# DACs.net
KiCad netlist of a schematic drawn in Altium Designer
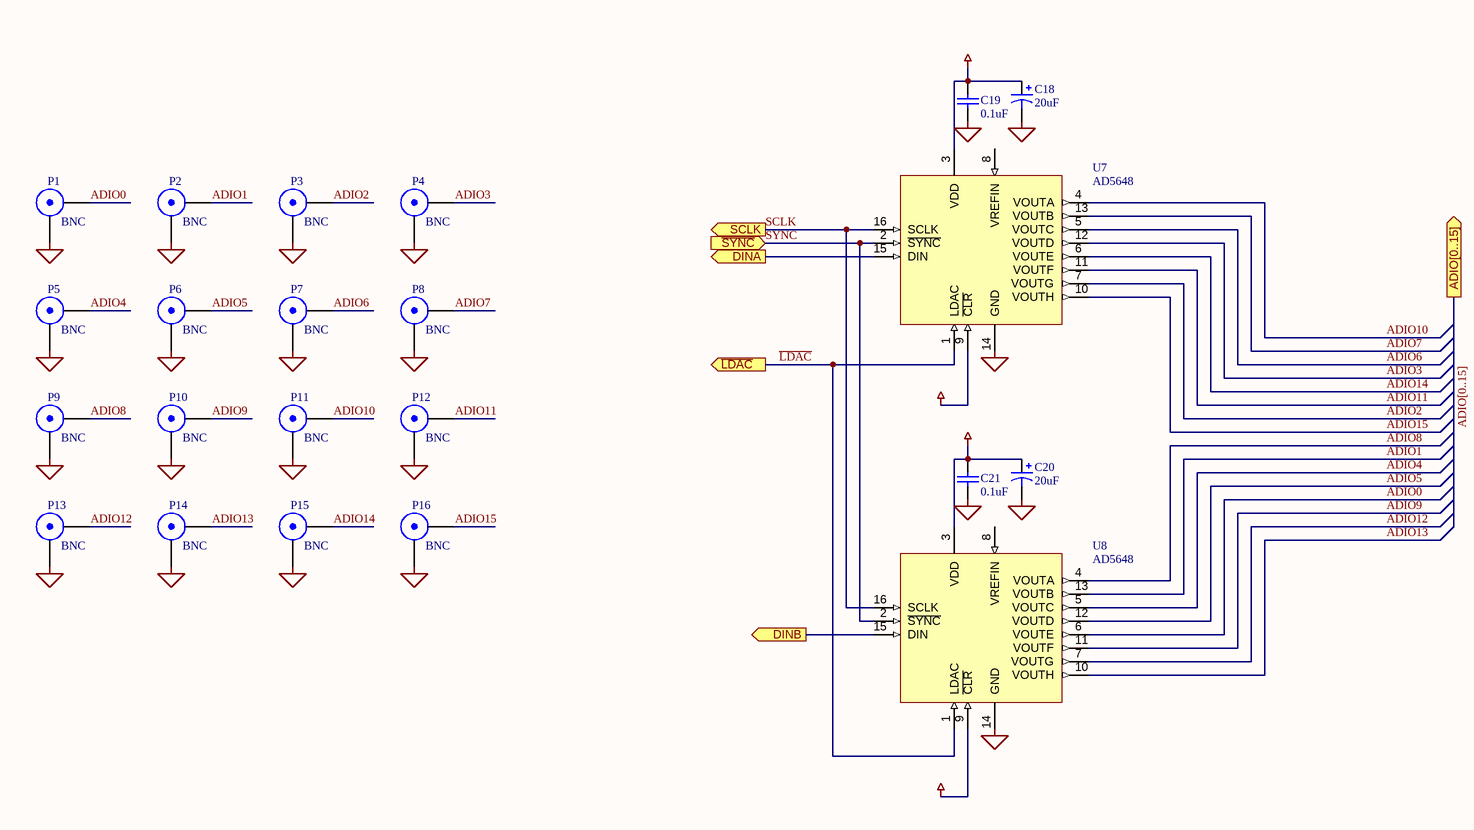
[diagram p0: DACs.SCHDOC]

(export (version "E")
  (design (tool "Eeschema 10.0.6"))
  (components
    (comp (ref "C18")
      (value "20uF")
      (footprint "C")
      (description "Polarized Capacitor (Radial)")
      (fields (field (name "Comment") "Cap Pol1") (field (name "PUBLISHER") "Altium Limited"))
      (libsource (lib "Miscellaneous Devices") (part "Cap Pol1"))
    )
    (comp (ref "C19")
      (value "0.1uF")
      (footprint "CC1005-0402")
      (description "Capacitor")
      (fields
        (field (name "MANUFACTURER") "Generic Components")
        (field (name "Comment") "Cap")
        (field (name "PUBLISHER") "Altium Limited")
      )
      (libsource (lib "Miscellaneous Devices") (part "Cap"))
    )
    (comp (ref "C20")
      (value "20uF")
      (footprint "C")
      (description "Polarized Capacitor (Radial)")
      (fields (field (name "Comment") "Cap Pol1") (field (name "PUBLISHER") "Altium Limited"))
      (libsource (lib "Miscellaneous Devices") (part "Cap Pol1"))
    )
    (comp (ref "C21")
      (value "0.1uF")
      (footprint "CC1005-0402")
      (description "Capacitor")
      (fields
        (field (name "MANUFACTURER") "Generic Components")
        (field (name "Comment") "Cap")
        (field (name "PUBLISHER") "Altium Limited")
      )
      (libsource (lib "Miscellaneous Devices") (part "Cap"))
    )
    (comp (ref "P1")
      (value "BNC")
      (footprint "Vertical BNC 227699-1")
      (description "BNC Elbow Connector")
      (fields (field (name "MANUFACTURER") "Generic Components") (field (name "PUBLISHER") "Altium Limited"))
      (libsource (lib "Miscellaneous Connectors") (part "BNC"))
    )
    (comp (ref "P2")
      (value "BNC")
      (footprint "Vertical BNC 227699-1")
      (description "BNC Elbow Connector")
      (fields (field (name "MANUFACTURER") "Generic Components") (field (name "PUBLISHER") "Altium Limited"))
      (libsource (lib "Miscellaneous Connectors") (part "BNC"))
    )
    (comp (ref "P3")
      (value "BNC")
      (footprint "Vertical BNC 227699-1")
      (description "BNC Elbow Connector")
      (fields (field (name "MANUFACTURER") "Generic Components") (field (name "PUBLISHER") "Altium Limited"))
      (libsource (lib "Miscellaneous Connectors") (part "BNC"))
    )
    (comp (ref "P4")
      (value "BNC")
      (footprint "Vertical BNC 227699-1")
      (description "BNC Elbow Connector")
      (fields (field (name "MANUFACTURER") "Generic Components") (field (name "PUBLISHER") "Altium Limited"))
      (libsource (lib "Miscellaneous Connectors") (part "BNC"))
    )
    (comp (ref "P5")
      (value "BNC")
      (footprint "Vertical BNC 227699-1")
      (description "BNC Elbow Connector")
      (fields (field (name "MANUFACTURER") "Generic Components") (field (name "PUBLISHER") "Altium Limited"))
      (libsource (lib "Miscellaneous Connectors") (part "BNC"))
    )
    (comp (ref "P6")
      (value "BNC")
      (footprint "Vertical BNC 227699-1")
      (description "BNC Elbow Connector")
      (fields (field (name "MANUFACTURER") "Generic Components") (field (name "PUBLISHER") "Altium Limited"))
      (libsource (lib "Miscellaneous Connectors") (part "BNC"))
    )
    (comp (ref "P7")
      (value "BNC")
      (footprint "Vertical BNC 227699-1")
      (description "BNC Elbow Connector")
      (fields (field (name "MANUFACTURER") "Generic Components") (field (name "PUBLISHER") "Altium Limited"))
      (libsource (lib "Miscellaneous Connectors") (part "BNC"))
    )
    (comp (ref "P8")
      (value "BNC")
      (footprint "Vertical BNC 227699-1")
      (description "BNC Elbow Connector")
      (fields (field (name "MANUFACTURER") "Generic Components") (field (name "PUBLISHER") "Altium Limited"))
      (libsource (lib "Miscellaneous Connectors") (part "BNC"))
    )
    (comp (ref "P9")
      (value "BNC")
      (footprint "Vertical BNC 227699-1")
      (description "BNC Elbow Connector")
      (fields (field (name "MANUFACTURER") "Generic Components") (field (name "PUBLISHER") "Altium Limited"))
      (libsource (lib "Miscellaneous Connectors") (part "BNC"))
    )
    (comp (ref "P10")
      (value "BNC")
      (footprint "Vertical BNC 227699-1")
      (description "BNC Elbow Connector")
      (fields (field (name "MANUFACTURER") "Generic Components") (field (name "PUBLISHER") "Altium Limited"))
      (libsource (lib "Miscellaneous Connectors") (part "BNC"))
    )
    (comp (ref "P11")
      (value "BNC")
      (footprint "Vertical BNC 227699-1")
      (description "BNC Elbow Connector")
      (fields (field (name "MANUFACTURER") "Generic Components") (field (name "PUBLISHER") "Altium Limited"))
      (libsource (lib "Miscellaneous Connectors") (part "BNC"))
    )
    (comp (ref "P12")
      (value "BNC")
      (footprint "Vertical BNC 227699-1")
      (description "BNC Elbow Connector")
      (fields (field (name "MANUFACTURER") "Generic Components") (field (name "PUBLISHER") "Altium Limited"))
      (libsource (lib "Miscellaneous Connectors") (part "BNC"))
    )
    (comp (ref "P13")
      (value "BNC")
      (footprint "Vertical BNC 227699-1")
      (description "BNC Elbow Connector")
      (fields (field (name "MANUFACTURER") "Generic Components") (field (name "PUBLISHER") "Altium Limited"))
      (libsource (lib "Miscellaneous Connectors") (part "BNC"))
    )
    (comp (ref "P14")
      (value "BNC")
      (footprint "Vertical BNC 227699-1")
      (description "BNC Elbow Connector")
      (fields (field (name "MANUFACTURER") "Generic Components") (field (name "PUBLISHER") "Altium Limited"))
      (libsource (lib "Miscellaneous Connectors") (part "BNC"))
    )
    (comp (ref "P15")
      (value "BNC")
      (footprint "Vertical BNC 227699-1")
      (description "BNC Elbow Connector")
      (fields (field (name "MANUFACTURER") "Generic Components") (field (name "PUBLISHER") "Altium Limited"))
      (libsource (lib "Miscellaneous Connectors") (part "BNC"))
    )
    (comp (ref "P16")
      (value "BNC")
      (footprint "Vertical BNC 227699-1")
      (description "BNC Elbow Connector")
      (fields (field (name "MANUFACTURER") "Generic Components") (field (name "PUBLISHER") "Altium Limited"))
      (libsource (lib "Miscellaneous Connectors") (part "BNC"))
    )
    (comp (ref "U7")
      (value "AD5648")
      (footprint "TSSO5x6-G16")
      (description "AD 14-bit DAC")
      (libsource (lib "parts") (part "AD5648BRUZ-2"))
    )
    (comp (ref "U8")
      (value "AD5648")
      (footprint "TSSO5x6-G16")
      (description "AD 14-bit DAC")
      (libsource (lib "parts") (part "AD5648BRUZ-2"))
    )
  )
  (nets
    (net (code "1") (name "/ADIO0") (class "Default")
      (node (ref "P1") (pin "1") (pinfunction "X_1") (pintype "passive"))
      (node (ref "U8") (pin "6") (pinfunction "VOUTE_6") (pintype "output"))
    )
    (net (code "2") (name "/ADIO1") (class "Default")
      (node (ref "P2") (pin "1") (pinfunction "X_1") (pintype "passive"))
      (node (ref "U8") (pin "13") (pinfunction "VOUTB_13") (pintype "output"))
    )
    (net (code "3") (name "/ADIO2") (class "Default")
      (node (ref "P3") (pin "1") (pinfunction "X_1") (pintype "passive"))
      (node (ref "U7") (pin "7") (pinfunction "VOUTG_7") (pintype "output"))
    )
    (net (code "4") (name "/ADIO3") (class "Default")
      (node (ref "P4") (pin "1") (pinfunction "X_1") (pintype "passive"))
      (node (ref "U7") (pin "12") (pinfunction "VOUTD_12") (pintype "output"))
    )
    (net (code "5") (name "/ADIO4") (class "Default")
      (node (ref "P5") (pin "1") (pinfunction "X_1") (pintype "passive"))
      (node (ref "U8") (pin "5") (pinfunction "VOUTC_5") (pintype "output"))
    )
    (net (code "6") (name "/ADIO5") (class "Default")
      (node (ref "P6") (pin "1") (pinfunction "X_1") (pintype "passive"))
      (node (ref "U8") (pin "12") (pinfunction "VOUTD_12") (pintype "output"))
    )
    (net (code "7") (name "/ADIO6") (class "Default")
      (node (ref "P7") (pin "1") (pinfunction "X_1") (pintype "passive"))
      (node (ref "U7") (pin "5") (pinfunction "VOUTC_5") (pintype "output"))
    )
    (net (code "8") (name "/ADIO7") (class "Default")
      (node (ref "P8") (pin "1") (pinfunction "X_1") (pintype "passive"))
      (node (ref "U7") (pin "13") (pinfunction "VOUTB_13") (pintype "output"))
    )
    (net (code "9") (name "/ADIO8") (class "Default")
      (node (ref "P9") (pin "1") (pinfunction "X_1") (pintype "passive"))
      (node (ref "U8") (pin "4") (pinfunction "VOUTA_4") (pintype "output"))
    )
    (net (code "10") (name "/ADIO9") (class "Default")
      (node (ref "P10") (pin "1") (pinfunction "X_1") (pintype "passive"))
      (node (ref "U8") (pin "11") (pinfunction "VOUTF_11") (pintype "output"))
    )
    (net (code "11") (name "/ADIO10") (class "Default")
      (node (ref "P11") (pin "1") (pinfunction "X_1") (pintype "passive"))
      (node (ref "U7") (pin "4") (pinfunction "VOUTA_4") (pintype "output"))
    )
    (net (code "12") (name "/ADIO11") (class "Default")
      (node (ref "P12") (pin "1") (pinfunction "X_1") (pintype "passive"))
      (node (ref "U7") (pin "11") (pinfunction "VOUTF_11") (pintype "output"))
    )
    (net (code "13") (name "/ADIO12") (class "Default")
      (node (ref "P13") (pin "1") (pinfunction "X_1") (pintype "passive"))
      (node (ref "U8") (pin "7") (pinfunction "VOUTG_7") (pintype "output"))
    )
    (net (code "14") (name "/ADIO13") (class "Default")
      (node (ref "P14") (pin "1") (pinfunction "X_1") (pintype "passive"))
      (node (ref "U8") (pin "10") (pinfunction "VOUTH_10") (pintype "output"))
    )
    (net (code "15") (name "/ADIO14") (class "Default")
      (node (ref "P15") (pin "1") (pinfunction "X_1") (pintype "passive"))
      (node (ref "U7") (pin "6") (pinfunction "VOUTE_6") (pintype "output"))
    )
    (net (code "16") (name "/ADIO15") (class "Default")
      (node (ref "P16") (pin "1") (pinfunction "X_1") (pintype "passive"))
      (node (ref "U7") (pin "10") (pinfunction "VOUTH_10") (pintype "output"))
    )
    (net (code "18") (name "/DINA") (class "Default")
      (node (ref "U7") (pin "15") (pinfunction "DIN_15") (pintype "input"))
    )
    (net (code "19") (name "/DINB") (class "Default")
      (node (ref "U8") (pin "15") (pinfunction "DIN_15") (pintype "input"))
    )
    (net (code "20") (name "/SCLK") (class "Default")
      (node (ref "U7") (pin "16") (pinfunction "SCLK_16") (pintype "input"))
      (node (ref "U8") (pin "16") (pinfunction "SCLK_16") (pintype "input"))
    )
    (net (code "21") (name "/~{LDAC}") (class "Default")
      (node (ref "U7") (pin "1") (pinfunction "LDAC_1") (pintype "input"))
      (node (ref "U8") (pin "1") (pinfunction "LDAC_1") (pintype "input"))
    )
    (net (code "22") (name "/~{SYNC}") (class "Default")
      (node (ref "U7") (pin "2") (pinfunction "~{SYNC}_2") (pintype "input"))
      (node (ref "U8") (pin "2") (pinfunction "~{SYNC}_2") (pintype "input"))
    )
    (net (code "23") (name "AGND") (class "Default")
      (node (ref "P1") (pin "2") (pinfunction "Y_2") (pintype "passive"))
      (node (ref "P10") (pin "2") (pinfunction "Y_2") (pintype "passive"))
      (node (ref "P11") (pin "2") (pinfunction "Y_2") (pintype "passive"))
      (node (ref "P12") (pin "2") (pinfunction "Y_2") (pintype "passive"))
      (node (ref "P13") (pin "2") (pinfunction "Y_2") (pintype "passive"))
      (node (ref "P14") (pin "2") (pinfunction "Y_2") (pintype "passive"))
      (node (ref "P15") (pin "2") (pinfunction "Y_2") (pintype "passive"))
      (node (ref "P16") (pin "2") (pinfunction "Y_2") (pintype "passive"))
      (node (ref "P2") (pin "2") (pinfunction "Y_2") (pintype "passive"))
      (node (ref "P3") (pin "2") (pinfunction "Y_2") (pintype "passive"))
      (node (ref "P4") (pin "2") (pinfunction "Y_2") (pintype "passive"))
      (node (ref "P5") (pin "2") (pinfunction "Y_2") (pintype "passive"))
      (node (ref "P6") (pin "2") (pinfunction "Y_2") (pintype "passive"))
      (node (ref "P7") (pin "2") (pinfunction "Y_2") (pintype "passive"))
      (node (ref "P8") (pin "2") (pinfunction "Y_2") (pintype "passive"))
      (node (ref "P9") (pin "2") (pinfunction "Y_2") (pintype "passive"))
    )
    (net (code "24") (name "AVDD") (class "Default")
      (node (ref "C18") (pin "1") (pinfunction "1_1") (pintype "passive"))
      (node (ref "C19") (pin "2") (pinfunction "2_2") (pintype "passive"))
      (node (ref "C20") (pin "1") (pinfunction "1_1") (pintype "passive"))
      (node (ref "C21") (pin "2") (pinfunction "2_2") (pintype "passive"))
      (node (ref "U7") (pin "3") (pinfunction "VDD_3") (pintype "power_in"))
      (node (ref "U7") (pin "9") (pinfunction "~{CLR}_9") (pintype "input"))
      (node (ref "U8") (pin "3") (pinfunction "VDD_3") (pintype "power_in"))
      (node (ref "U8") (pin "9") (pinfunction "~{CLR}_9") (pintype "input"))
    )
    (net (code "25") (name "GND") (class "Default")
      (node (ref "C18") (pin "2") (pinfunction "2_2") (pintype "passive"))
      (node (ref "C19") (pin "1") (pinfunction "1_1") (pintype "passive"))
      (node (ref "C20") (pin "2") (pinfunction "2_2") (pintype "passive"))
      (node (ref "C21") (pin "1") (pinfunction "1_1") (pintype "passive"))
      (node (ref "U7") (pin "14") (pinfunction "GND_14") (pintype "power_in"))
      (node (ref "U8") (pin "14") (pinfunction "GND_14") (pintype "power_in"))
    )
    (net (code "26") (name "unconnected-(U7-VREFIN-Pad8)") (class "Default")
      (node (ref "U7") (pin "8") (pinfunction "VREFIN_8") (pintype "input"))
    )
    (net (code "27") (name "unconnected-(U8-VREFIN-Pad8)") (class "Default")
      (node (ref "U8") (pin "8") (pinfunction "VREFIN_8") (pintype "input"))
    )
  )
)
